# Schematic.net
KiCad netlist of a schematic drawn in EasyEDA
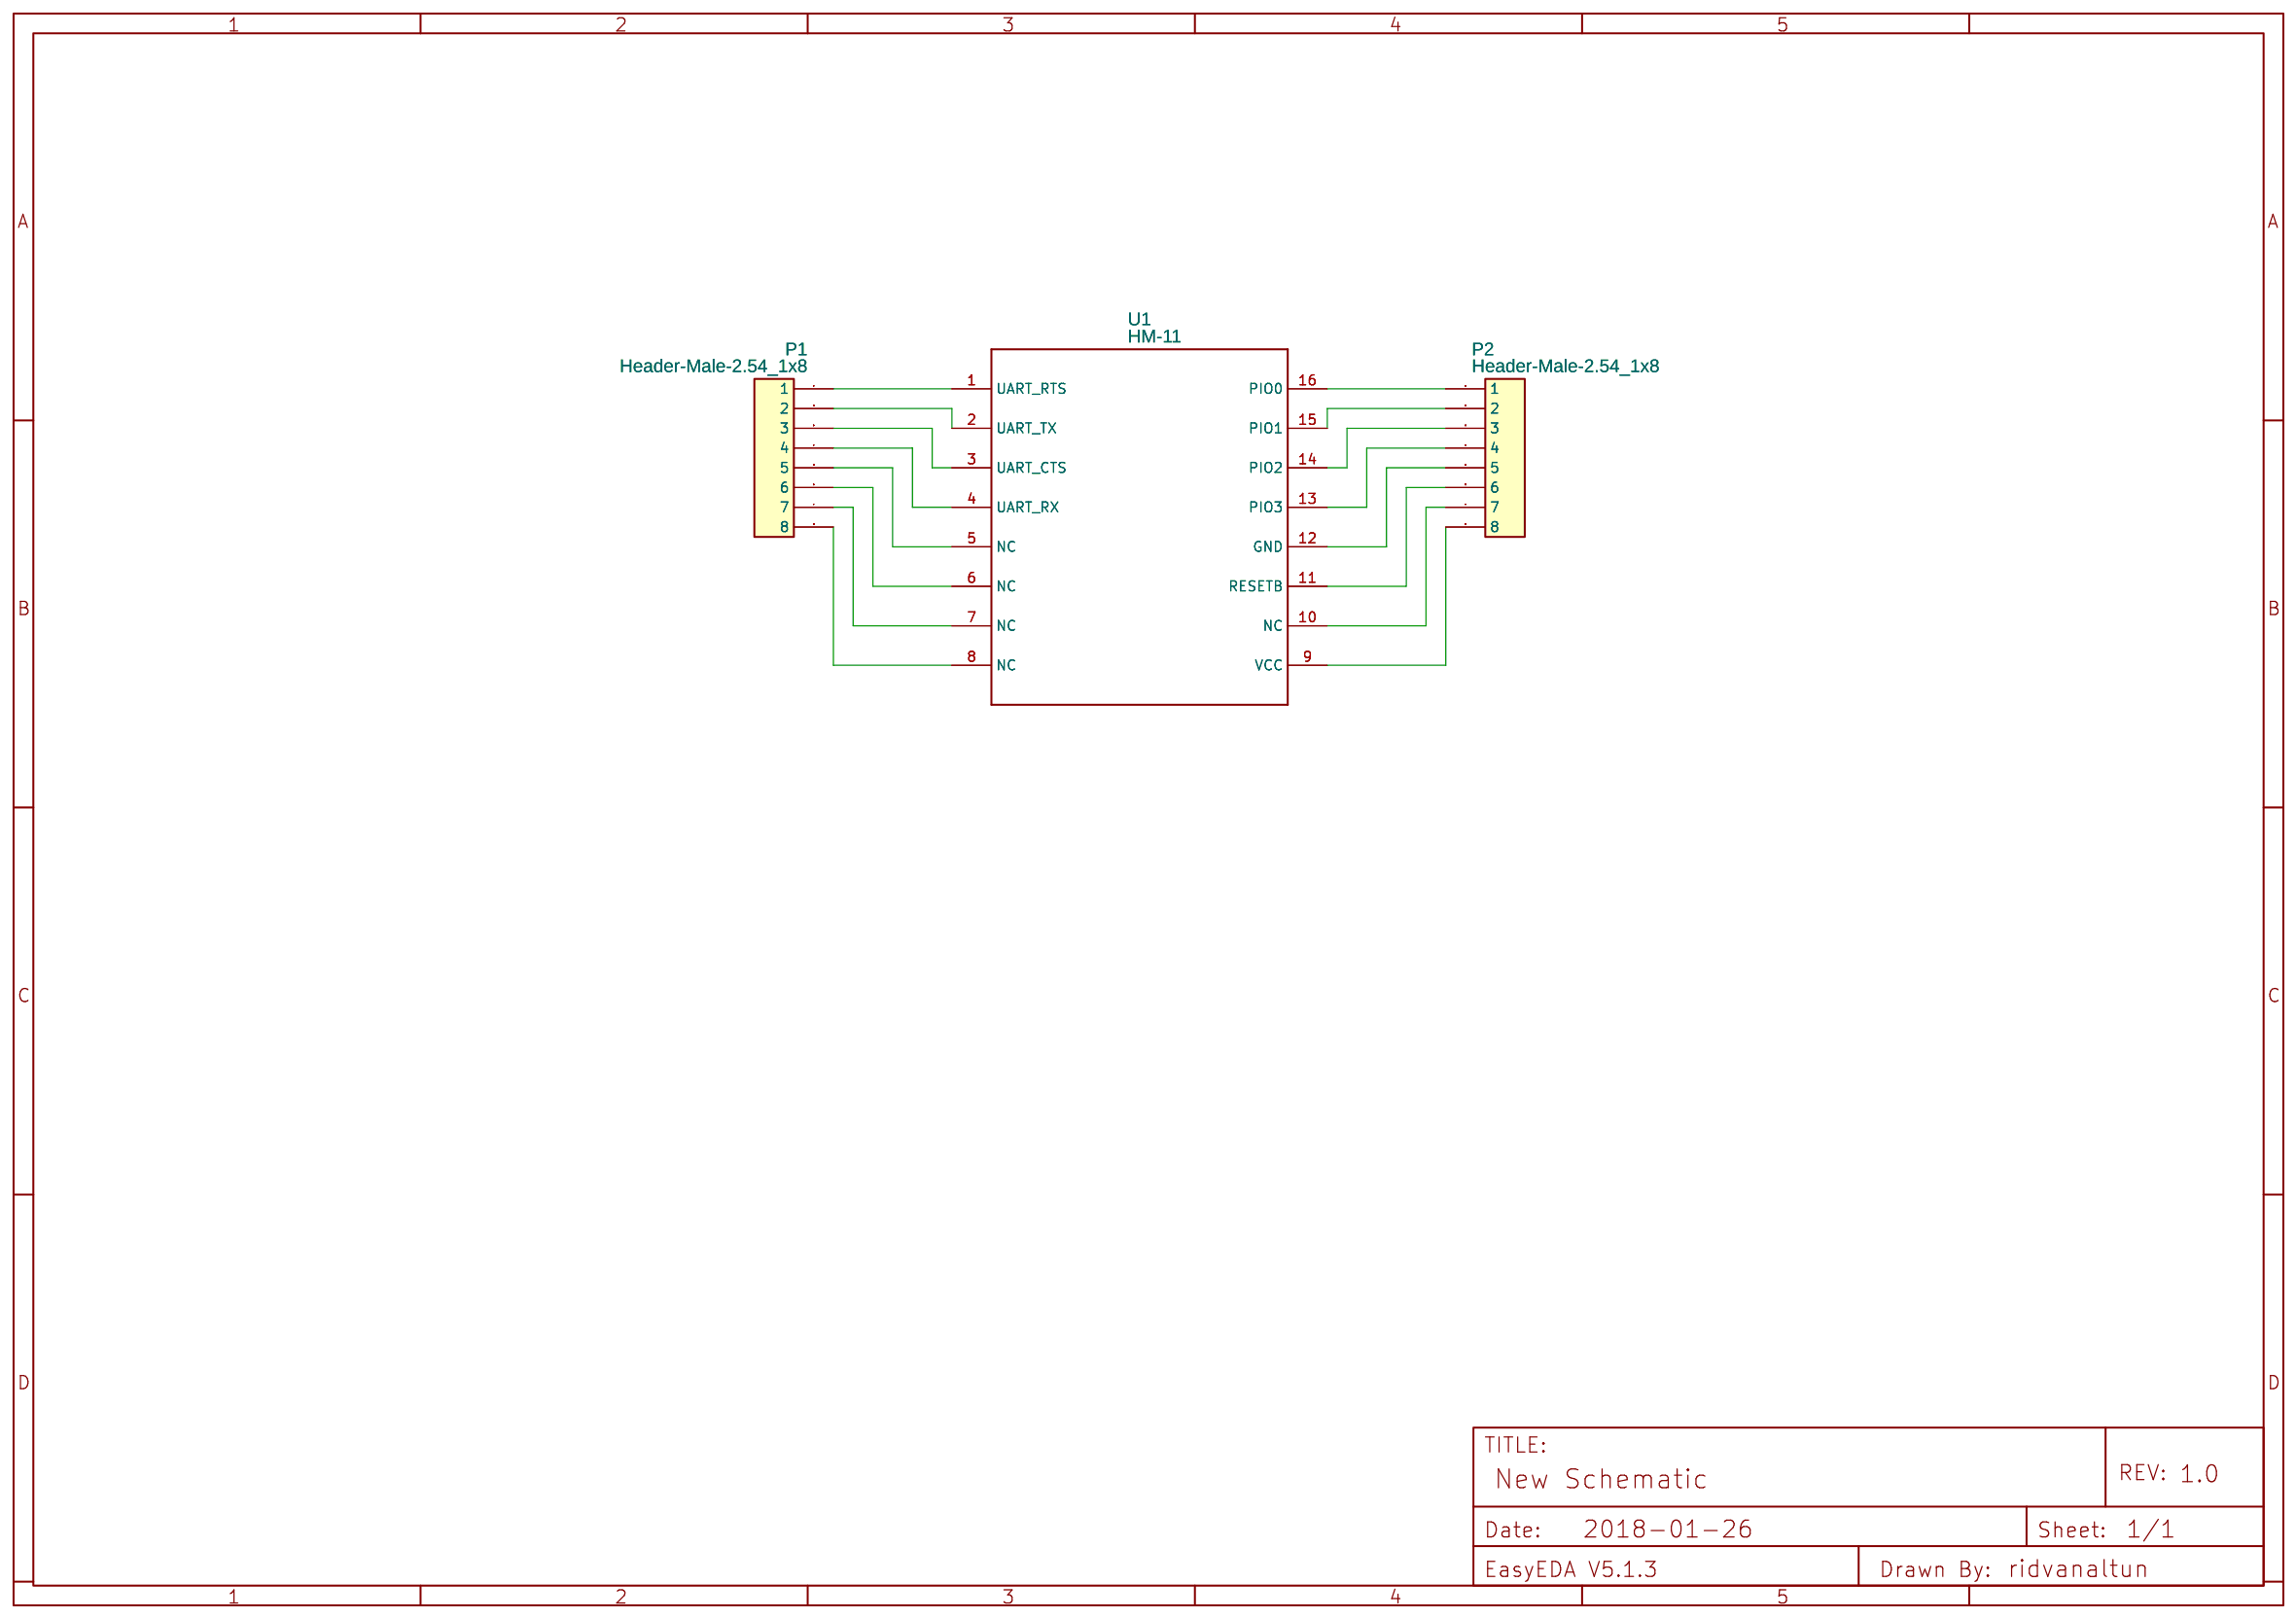
[diagram p0: schematic sheet]

(export (version "E")
  (design (tool "Eeschema 10.0.6"))
  (components
    (comp (ref "P1") (value "Header-Male-2.54_1x8") (libsource (lib "") (part "Unknown_400_225")))
    (comp (ref "P2") (value "Header-Male-2.54_1x8") (libsource (lib "") (part "Unknown_740_225")))
    (comp (ref "U1")
      (value "HM-11")
      (fields (field (name "BOM_Manufacturer Part") "?"))
      (libsource (lib "") (part "Unknown_475_350"))
    )
  )
  (nets
    (net (code "1") (name "Net-(P1-Pad5)") (class "Default")
      (node (ref "P1") (pin "5") (pinfunction "5_5") (pintype "input"))
      (node (ref "U1") (pin "5") (pinfunction "NC_5") (pintype "unspecified"))
    )
    (net (code "2") (name "Net-(P1-Pad6)") (class "Default")
      (node (ref "P1") (pin "6") (pinfunction "6_6") (pintype "input"))
      (node (ref "U1") (pin "6") (pinfunction "NC_6") (pintype "unspecified"))
    )
    (net (code "3") (name "Net-(P1-Pad7)") (class "Default")
      (node (ref "P1") (pin "7") (pinfunction "7_7") (pintype "input"))
      (node (ref "U1") (pin "7") (pinfunction "NC_7") (pintype "unspecified"))
    )
    (net (code "4") (name "Net-(P1-Pad8)") (class "Default")
      (node (ref "P1") (pin "8") (pinfunction "8_8") (pintype "input"))
      (node (ref "U1") (pin "8") (pinfunction "NC_8") (pintype "unspecified"))
    )
    (net (code "5") (name "Net-(P2-Pad7)") (class "Default")
      (node (ref "P2") (pin "7") (pinfunction "7_7") (pintype "input"))
      (node (ref "U1") (pin "10") (pinfunction "NC_10") (pintype "unspecified"))
    )
    (net (code "6") (name "Net-(U1-GND)") (class "Default")
      (node (ref "P2") (pin "5") (pinfunction "5_5") (pintype "input"))
      (node (ref "U1") (pin "12") (pinfunction "GND_12") (pintype "unspecified"))
    )
    (net (code "7") (name "Net-(U1-PIO0)") (class "Default")
      (node (ref "P2") (pin "1") (pinfunction "1_1") (pintype "input"))
      (node (ref "U1") (pin "16") (pinfunction "PIO0_16") (pintype "unspecified"))
    )
    (net (code "8") (name "Net-(U1-PIO1)") (class "Default")
      (node (ref "P2") (pin "2") (pinfunction "2_2") (pintype "input"))
      (node (ref "U1") (pin "15") (pinfunction "PIO1_15") (pintype "unspecified"))
    )
    (net (code "9") (name "Net-(U1-PIO2)") (class "Default")
      (node (ref "P2") (pin "3") (pinfunction "3_3") (pintype "input"))
      (node (ref "U1") (pin "14") (pinfunction "PIO2_14") (pintype "unspecified"))
    )
    (net (code "10") (name "Net-(U1-PIO3)") (class "Default")
      (node (ref "P2") (pin "4") (pinfunction "4_4") (pintype "input"))
      (node (ref "U1") (pin "13") (pinfunction "PIO3_13") (pintype "unspecified"))
    )
    (net (code "11") (name "Net-(U1-RESETB)") (class "Default")
      (node (ref "P2") (pin "6") (pinfunction "6_6") (pintype "input"))
      (node (ref "U1") (pin "11") (pinfunction "RESETB_11") (pintype "unspecified"))
    )
    (net (code "12") (name "Net-(U1-UART_CTS)") (class "Default")
      (node (ref "P1") (pin "3") (pinfunction "3_3") (pintype "input"))
      (node (ref "U1") (pin "3") (pinfunction "UART_CTS_3") (pintype "unspecified"))
    )
    (net (code "13") (name "Net-(U1-UART_RTS)") (class "Default")
      (node (ref "P1") (pin "1") (pinfunction "1_1") (pintype "input"))
      (node (ref "U1") (pin "1") (pinfunction "UART_RTS_1") (pintype "unspecified"))
    )
    (net (code "14") (name "Net-(U1-UART_RX)") (class "Default")
      (node (ref "P1") (pin "4") (pinfunction "4_4") (pintype "input"))
      (node (ref "U1") (pin "4") (pinfunction "UART_RX_4") (pintype "unspecified"))
    )
    (net (code "15") (name "Net-(U1-UART_TX)") (class "Default")
      (node (ref "P1") (pin "2") (pinfunction "2_2") (pintype "input"))
      (node (ref "U1") (pin "2") (pinfunction "UART_TX_2") (pintype "unspecified"))
    )
    (net (code "16") (name "Net-(U1-VCC)") (class "Default")
      (node (ref "P2") (pin "8") (pinfunction "8_8") (pintype "input"))
      (node (ref "U1") (pin "9") (pinfunction "VCC_9") (pintype "unspecified"))
    )
  )
)
